# Turntable.net
KiCad netlist of a schematic drawn in EAGLE
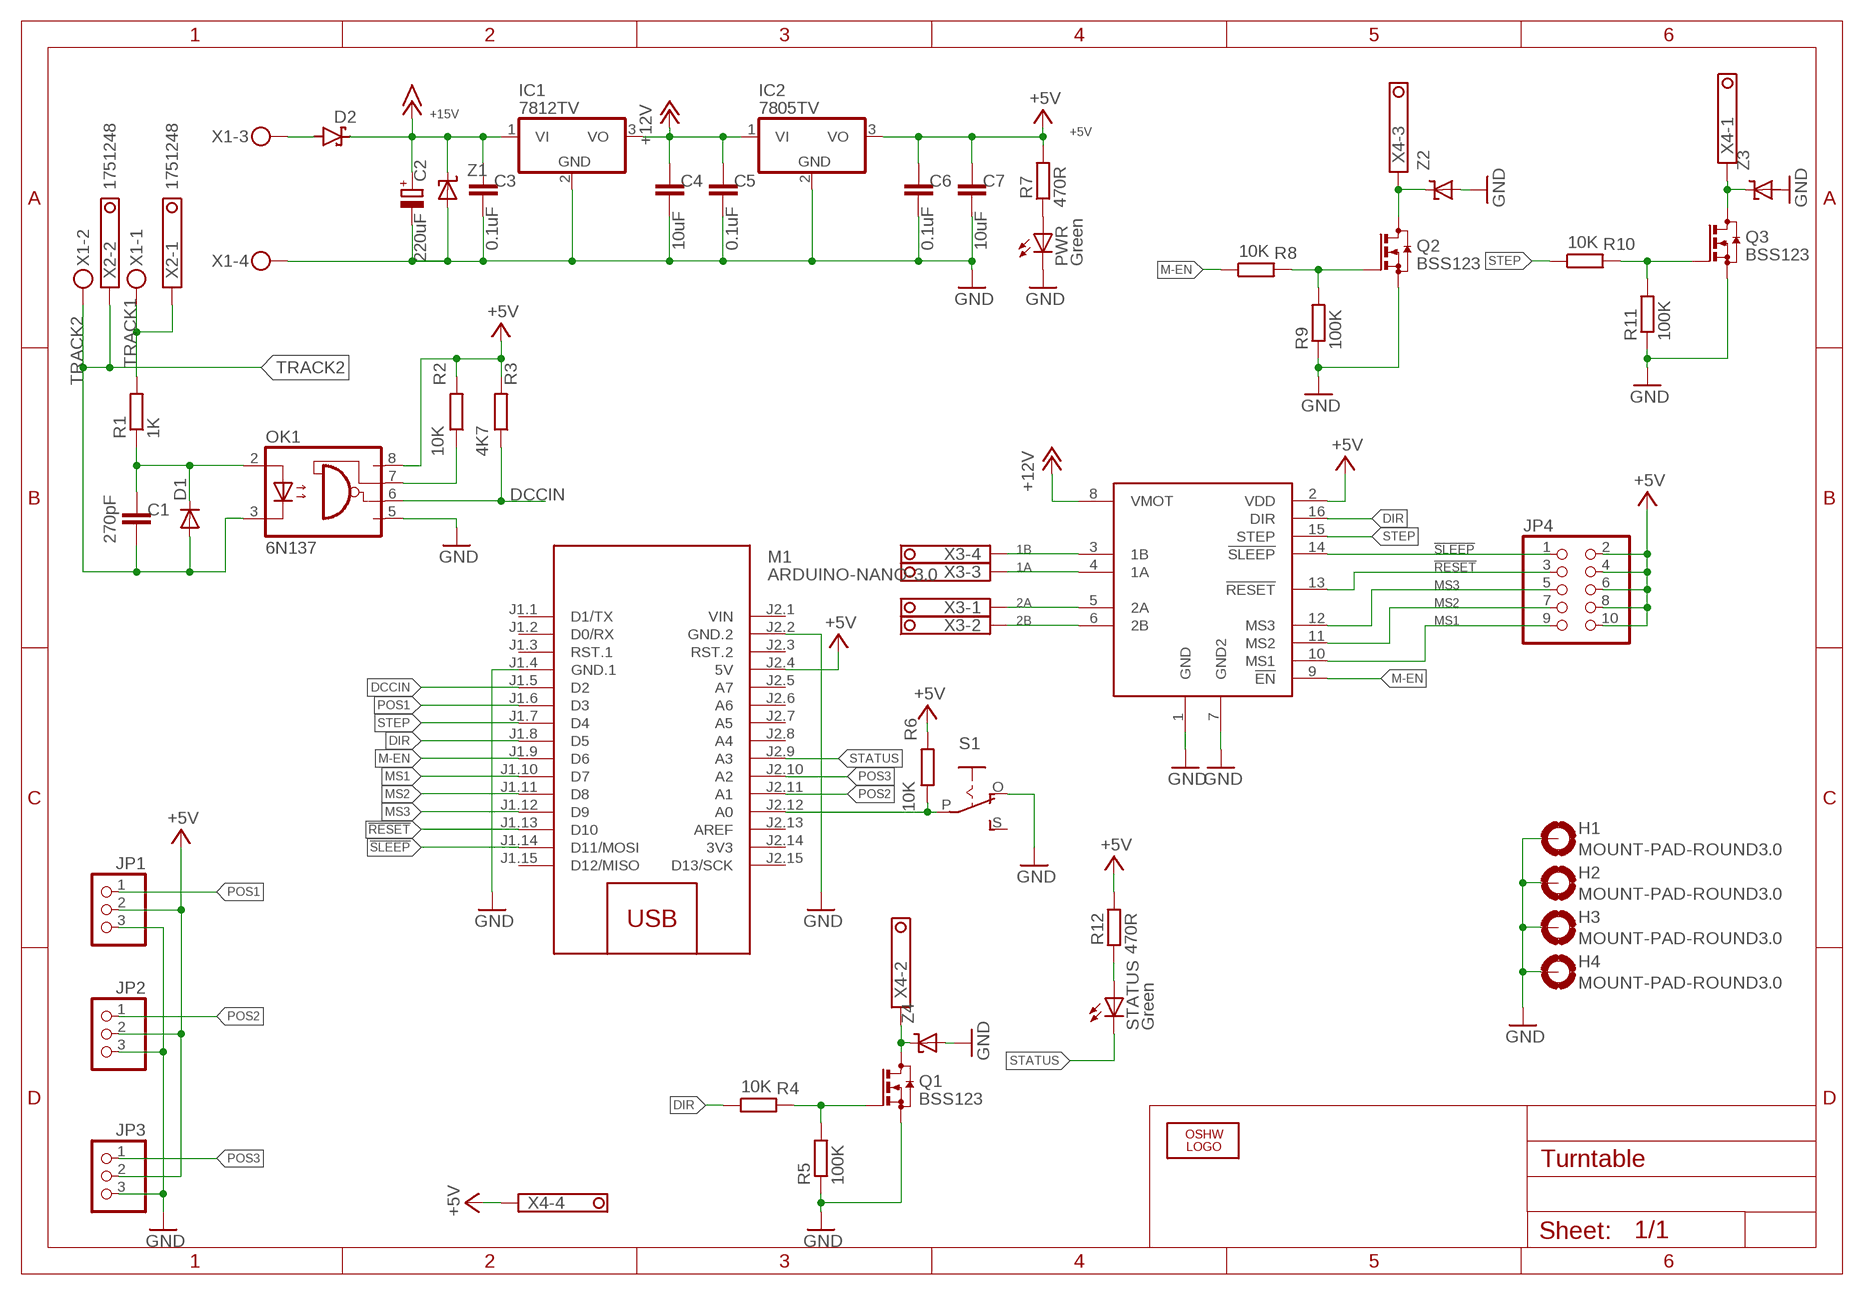
[diagram p0: schematic, sheet 1]

(export (version "E")
  (design (tool "Eeschema 10.0.6"))
  (components
    (comp (ref "C1")
      (value "270pF")
      (footprint "eagle-import:0805")
      (libsource (lib "eagle-import") (part "CAPACITOR-0805"))
    )
    (comp (ref "C2")
      (value "220uF")
      (footprint "eagle-import:E7,5-16")
      (libsource (lib "eagle-import") (part "CPOL-EUE7.5-16"))
    )
    (comp (ref "C3")
      (value "0.1uF")
      (footprint "eagle-import:0805")
      (libsource (lib "eagle-import") (part "CAPACITOR-0805"))
    )
    (comp (ref "C4")
      (value "10uF")
      (footprint "eagle-import:0805")
      (libsource (lib "eagle-import") (part "CAPACITOR-0805"))
    )
    (comp (ref "C5")
      (value "0.1uF")
      (footprint "eagle-import:0805")
      (libsource (lib "eagle-import") (part "CAPACITOR-0805"))
    )
    (comp (ref "C6")
      (value "0.1uF")
      (footprint "eagle-import:0805")
      (libsource (lib "eagle-import") (part "CAPACITOR-0805"))
    )
    (comp (ref "C7")
      (value "10uF")
      (footprint "eagle-import:0805")
      (libsource (lib "eagle-import") (part "CAPACITOR-0805"))
    )
    (comp (ref "D1")
      (value "CGRM4002-G")
      (footprint "eagle-import:SOD-123_MINI-SMA")
      (libsource (lib "eagle-import") (part "CGRM400-G2"))
    )
    (comp (ref "D2")
      (value "SCHOTTKY-DIODESMD")
      (footprint "eagle-import:SMB")
      (libsource (lib "eagle-import") (part "SCHOTTKY-DIODESMD"))
    )
    (comp (ref "H1")
      (value "MOUNT-PAD-ROUND3.0")
      (footprint "eagle-import:3,0-PAD")
      (libsource (lib "eagle-import") (part "MOUNT-PAD-ROUND3.0"))
    )
    (comp (ref "H2")
      (value "MOUNT-PAD-ROUND3.0")
      (footprint "eagle-import:3,0-PAD")
      (libsource (lib "eagle-import") (part "MOUNT-PAD-ROUND3.0"))
    )
    (comp (ref "H3")
      (value "MOUNT-PAD-ROUND3.0")
      (footprint "eagle-import:3,0-PAD")
      (libsource (lib "eagle-import") (part "MOUNT-PAD-ROUND3.0"))
    )
    (comp (ref "H4")
      (value "MOUNT-PAD-ROUND3.0")
      (footprint "eagle-import:3,0-PAD")
      (libsource (lib "eagle-import") (part "MOUNT-PAD-ROUND3.0"))
    )
    (comp (ref "IC1")
      (value "7812TV")
      (footprint "eagle-import:TO220V")
      (libsource (lib "eagle-import") (part "78TV12"))
    )
    (comp (ref "IC2")
      (value "7805TV")
      (footprint "eagle-import:TO220V")
      (libsource (lib "eagle-import") (part "78TV05"))
    )
    (comp (ref "JP1")
      (value "PINHD-1X3")
      (footprint "eagle-import:1X03")
      (libsource (lib "eagle-import") (part "PINHD-1X3"))
    )
    (comp (ref "JP2")
      (value "PINHD-1X3")
      (footprint "eagle-import:1X03")
      (libsource (lib "eagle-import") (part "PINHD-1X3"))
    )
    (comp (ref "JP3")
      (value "PINHD-1X3")
      (footprint "eagle-import:1X03")
      (libsource (lib "eagle-import") (part "PINHD-1X3"))
    )
    (comp (ref "JP4")
      (value "PINHD-2X5")
      (footprint "eagle-import:2X05")
      (libsource (lib "eagle-import") (part "PINHD-2X5"))
    )
    (comp (ref "LOGO1")
      (value "OSHW_LOGO_6MILX0200-NT")
      (footprint "eagle-import:OSHW_6X200_NOTEXT")
      (libsource (lib "eagle-import") (part "OSHW_LOGO_6MILX0200-NT"))
    )
    (comp (ref "M1")
      (value "ARDUINO-NANO-3.0")
      (footprint "eagle-import:ARDUINO-NANO-3.0")
      (libsource (lib "eagle-import") (part "ARDUINO-NANO-3.0"))
    )
    (comp (ref "OK1")
      (value "6N137")
      (footprint "eagle-import:DIL08")
      (libsource (lib "eagle-import") (part "6N137"))
    )
    (comp (ref "PWR")
      (value "Green")
      (footprint "eagle-import:LED3MM")
      (libsource (lib "eagle-import") (part "LED3MM"))
    )
    (comp (ref "Q1")
      (value "BSS123")
      (footprint "eagle-import:SOT23")
      (libsource (lib "eagle-import") (part "BSS123"))
    )
    (comp (ref "Q2")
      (value "BSS123")
      (footprint "eagle-import:SOT23")
      (libsource (lib "eagle-import") (part "BSS123"))
    )
    (comp (ref "Q3")
      (value "BSS123")
      (footprint "eagle-import:SOT23")
      (libsource (lib "eagle-import") (part "BSS123"))
    )
    (comp (ref "R1")
      (value "1K")
      (footprint "eagle-import:R0805")
      (libsource (lib "eagle-import") (part "RESISTORR0805-3D"))
    )
    (comp (ref "R2")
      (value "10K")
      (footprint "eagle-import:R0805")
      (libsource (lib "eagle-import") (part "RESISTORR0805-3D"))
    )
    (comp (ref "R3")
      (value "4K7")
      (footprint "eagle-import:R0805")
      (libsource (lib "eagle-import") (part "RESISTORR0805-3D"))
    )
    (comp (ref "R4")
      (value "10K")
      (footprint "eagle-import:R0805")
      (libsource (lib "eagle-import") (part "RESISTORR0805-3D"))
    )
    (comp (ref "R5")
      (value "100K")
      (footprint "eagle-import:R0805")
      (libsource (lib "eagle-import") (part "RESISTORR0805-3D"))
    )
    (comp (ref "R6")
      (value "10K")
      (footprint "eagle-import:R0805")
      (libsource (lib "eagle-import") (part "RESISTORR0805-3D"))
    )
    (comp (ref "R7")
      (value "470R")
      (footprint "eagle-import:R0805")
      (libsource (lib "eagle-import") (part "RESISTORR0805-3D"))
    )
    (comp (ref "R8")
      (value "10K")
      (footprint "eagle-import:R0805")
      (libsource (lib "eagle-import") (part "RESISTORR0805-3D"))
    )
    (comp (ref "R9")
      (value "100K")
      (footprint "eagle-import:R0805")
      (libsource (lib "eagle-import") (part "RESISTORR0805-3D"))
    )
    (comp (ref "R10")
      (value "10K")
      (footprint "eagle-import:R0805")
      (libsource (lib "eagle-import") (part "RESISTORR0805-3D"))
    )
    (comp (ref "R11")
      (value "100K")
      (footprint "eagle-import:R0805")
      (libsource (lib "eagle-import") (part "RESISTORR0805-3D"))
    )
    (comp (ref "R12")
      (value "470R")
      (footprint "eagle-import:R0805")
      (libsource (lib "eagle-import") (part "RESISTORR0805-3D"))
    )
    (comp (ref "S1")
      (value "EG1218S")
      (footprint "eagle-import:EG1218")
      (libsource (lib "eagle-import") (part "EG1218S"))
    )
    (comp (ref "STATUS")
      (value "Green")
      (footprint "eagle-import:LED3MM")
      (libsource (lib "eagle-import") (part "LED3MM"))
    )
    (comp (ref "U1")
      (value "A4988")
      (footprint "eagle-import:POLOLUA4988")
      (libsource (lib "eagle-import") (part "A4988"))
    )
    (comp (ref "X1")
      (value "MKDSN1,5/4-5,08")
      (footprint "eagle-import:MKDSN1,5_4-5,08")
      (fields (field (name "MPN") "SMKDSN1,5/4-5,08"))
      (libsource (lib "eagle-import") (part "MKDSN1,5/4-5,08"))
    )
    (comp (ref "X2")
      (value "1751248")
      (footprint "eagle-import:1751248")
      (libsource (lib "eagle-import") (part "1751248"))
    )
    (comp (ref "X3")
      (value "1751264")
      (footprint "eagle-import:1751264")
      (libsource (lib "eagle-import") (part "1751264"))
    )
    (comp (ref "X4")
      (value "1751264")
      (footprint "eagle-import:1751264")
      (libsource (lib "eagle-import") (part "1751264"))
    )
    (comp (ref "Z1")
      (value "MSMPX.X")
      (footprint "eagle-import:MICROSMP-T")
      (fields (field (name "MANUFACTURER") "VISHAY"))
      (libsource (lib "eagle-import") (part "MSMPX.X"))
    )
    (comp (ref "Z2")
      (value "MSMPX.X")
      (footprint "eagle-import:MICROSMP-T")
      (fields (field (name "MANUFACTURER") "VISHAY"))
      (libsource (lib "eagle-import") (part "MSMPX.X"))
    )
    (comp (ref "Z3")
      (value "MSMPX.X")
      (footprint "eagle-import:MICROSMP-T")
      (fields (field (name "MANUFACTURER") "VISHAY"))
      (libsource (lib "eagle-import") (part "MSMPX.X"))
    )
    (comp (ref "Z4")
      (value "MSMPX.X")
      (footprint "eagle-import:MICROSMP-T")
      (fields (field (name "MANUFACTURER") "VISHAY"))
      (libsource (lib "eagle-import") (part "MSMPX.X"))
    )
  )
  (nets
    (net (code "1") (name "+5V") (class "Default")
      (node (ref "C6") (pin "1") (pinfunction "1_1") (pintype "passive"))
      (node (ref "C7") (pin "1") (pinfunction "1_1") (pintype "passive"))
      (node (ref "IC2") (pin "3") (pinfunction "VO_3") (pintype "passive"))
      (node (ref "JP1") (pin "2") (pinfunction "2_2") (pintype "passive"))
      (node (ref "JP2") (pin "2") (pinfunction "2_2") (pintype "passive"))
      (node (ref "JP3") (pin "2") (pinfunction "2_2") (pintype "passive"))
      (node (ref "JP4") (pin "10") (pinfunction "10_10") (pintype "passive"))
      (node (ref "JP4") (pin "2") (pinfunction "2_2") (pintype "passive"))
      (node (ref "JP4") (pin "4") (pinfunction "4_4") (pintype "passive"))
      (node (ref "JP4") (pin "6") (pinfunction "6_6") (pintype "passive"))
      (node (ref "JP4") (pin "8") (pinfunction "8_8") (pintype "passive"))
      (node (ref "M1") (pin "J2.4") (pinfunction "5V_J2.4") (pintype "power_in"))
      (node (ref "OK1") (pin "8") (pinfunction "VCC_8") (pintype "passive"))
      (node (ref "R12") (pin "2") (pinfunction "2_2") (pintype "passive"))
      (node (ref "R2") (pin "2") (pinfunction "2_2") (pintype "passive"))
      (node (ref "R3") (pin "2") (pinfunction "2_2") (pintype "passive"))
      (node (ref "R6") (pin "2") (pinfunction "2_2") (pintype "passive"))
      (node (ref "R7") (pin "2") (pinfunction "2_2") (pintype "passive"))
      (node (ref "U1") (pin "2") (pinfunction "VDD_2") (pintype "power_in"))
      (node (ref "X4") (pin "4") (pinfunction "K_4") (pintype "passive"))
    )
    (net (code "2") (name "+12V") (class "Default")
      (node (ref "C4") (pin "1") (pinfunction "1_1") (pintype "passive"))
      (node (ref "C5") (pin "1") (pinfunction "1_1") (pintype "passive"))
      (node (ref "IC1") (pin "3") (pinfunction "VO_3") (pintype "passive"))
      (node (ref "IC2") (pin "1") (pinfunction "VI_1") (pintype "input"))
      (node (ref "U1") (pin "8") (pinfunction "VMOT_8") (pintype "bidirectional"))
    )
    (net (code "3") (name "+15V") (class "Default")
      (node (ref "C2") (pin "+") (pinfunction "+_+") (pintype "passive"))
      (node (ref "C3") (pin "1") (pinfunction "1_1") (pintype "passive"))
      (node (ref "D2") (pin "C") (pinfunction "C_C") (pintype "passive"))
      (node (ref "IC1") (pin "1") (pinfunction "VI_1") (pintype "input"))
      (node (ref "Z1") (pin "C") (pinfunction "C_C") (pintype "passive"))
    )
    (net (code "4") (name "/1A") (class "Default")
      (node (ref "U1") (pin "4") (pinfunction "1A_4") (pintype "open_collector"))
      (node (ref "X3") (pin "3") (pinfunction "K_3") (pintype "passive"))
    )
    (net (code "5") (name "/1B") (class "Default")
      (node (ref "U1") (pin "3") (pinfunction "1B_3") (pintype "open_collector"))
      (node (ref "X3") (pin "4") (pinfunction "K_4") (pintype "passive"))
    )
    (net (code "6") (name "/2A") (class "Default")
      (node (ref "U1") (pin "5") (pinfunction "2A_5") (pintype "open_collector"))
      (node (ref "X3") (pin "1") (pinfunction "K_1") (pintype "passive"))
    )
    (net (code "7") (name "/2B") (class "Default")
      (node (ref "U1") (pin "6") (pinfunction "2B_6") (pintype "open_collector"))
      (node (ref "X3") (pin "2") (pinfunction "K_2") (pintype "passive"))
    )
    (net (code "8") (name "/3V3") (class "Default")
      (node (ref "M1") (pin "J2.14") (pinfunction "3V3_J2.14") (pintype "power_in"))
    )
    (net (code "9") (name "/TRACK1") (class "Default")
      (node (ref "R1") (pin "2") (pinfunction "2_2") (pintype "passive"))
      (node (ref "X1") (pin "1") (pinfunction "KL_1") (pintype "passive"))
      (node (ref "X2") (pin "1") (pinfunction "K_1") (pintype "passive"))
    )
    (net (code "10") (name "/VIN") (class "Default")
      (node (ref "M1") (pin "J2.1") (pinfunction "VIN_J2.1") (pintype "power_in"))
    )
    (net (code "11") (name "/~{RESET}") (class "Default")
      (node (ref "JP4") (pin "3") (pinfunction "3_3") (pintype "passive"))
      (node (ref "M1") (pin "J1.13") (pinfunction "D10_J1.13") (pintype "bidirectional"))
      (node (ref "U1") (pin "13") (pinfunction "~{RESET}_13") (pintype "input"))
    )
    (net (code "12") (name "/~{SLEEP}") (class "Default")
      (node (ref "JP4") (pin "1") (pinfunction "1_1") (pintype "passive"))
      (node (ref "M1") (pin "J1.14") (pinfunction "D11/MOSI_J1.14") (pintype "bidirectional"))
      (node (ref "U1") (pin "14") (pinfunction "~{SLEEP}_14") (pintype "input"))
    )
    (net (code "13") (name "DCCIN") (class "Default")
      (node (ref "M1") (pin "J1.5") (pinfunction "D2_J1.5") (pintype "bidirectional"))
      (node (ref "OK1") (pin "6") (pinfunction "VO_6") (pintype "passive"))
      (node (ref "R3") (pin "1") (pinfunction "1_1") (pintype "passive"))
    )
    (net (code "14") (name "DIR") (class "Default")
      (node (ref "M1") (pin "J1.8") (pinfunction "D5_J1.8") (pintype "bidirectional"))
      (node (ref "R4") (pin "1") (pinfunction "1_1") (pintype "passive"))
      (node (ref "U1") (pin "16") (pinfunction "DIR_16") (pintype "input"))
    )
    (net (code "15") (name "GND") (class "Default")
      (node (ref "C2") (pin "-") (pinfunction "-_-") (pintype "passive"))
      (node (ref "C3") (pin "2") (pinfunction "2_2") (pintype "passive"))
      (node (ref "C4") (pin "2") (pinfunction "2_2") (pintype "passive"))
      (node (ref "C5") (pin "2") (pinfunction "2_2") (pintype "passive"))
      (node (ref "C6") (pin "2") (pinfunction "2_2") (pintype "passive"))
      (node (ref "C7") (pin "2") (pinfunction "2_2") (pintype "passive"))
      (node (ref "H1") (pin "B3,0") (pinfunction "MOUNT_B3,0") (pintype "passive"))
      (node (ref "H2") (pin "B3,0") (pinfunction "MOUNT_B3,0") (pintype "passive"))
      (node (ref "H3") (pin "B3,0") (pinfunction "MOUNT_B3,0") (pintype "passive"))
      (node (ref "H4") (pin "B3,0") (pinfunction "MOUNT_B3,0") (pintype "passive"))
      (node (ref "IC1") (pin "2") (pinfunction "GND_2") (pintype "passive"))
      (node (ref "IC2") (pin "2") (pinfunction "GND_2") (pintype "passive"))
      (node (ref "JP1") (pin "3") (pinfunction "3_3") (pintype "passive"))
      (node (ref "JP2") (pin "3") (pinfunction "3_3") (pintype "passive"))
      (node (ref "JP3") (pin "3") (pinfunction "3_3") (pintype "passive"))
      (node (ref "M1") (pin "J1.4") (pinfunction "GND.1_J1.4") (pintype "power_in"))
      (node (ref "M1") (pin "J2.2") (pinfunction "GND.2_J2.2") (pintype "power_in"))
      (node (ref "OK1") (pin "5") (pinfunction "GND_5") (pintype "passive"))
      (node (ref "PWR") (pin "K") (pinfunction "C_K") (pintype "passive"))
      (node (ref "Q1") (pin "2") (pinfunction "S_2") (pintype "passive"))
      (node (ref "Q2") (pin "2") (pinfunction "S_2") (pintype "passive"))
      (node (ref "Q3") (pin "2") (pinfunction "S_2") (pintype "passive"))
      (node (ref "R11") (pin "1") (pinfunction "1_1") (pintype "passive"))
      (node (ref "R5") (pin "1") (pinfunction "1_1") (pintype "passive"))
      (node (ref "R9") (pin "1") (pinfunction "1_1") (pintype "passive"))
      (node (ref "S1") (pin "O") (pinfunction "O_O") (pintype "passive"))
      (node (ref "U1") (pin "1") (pinfunction "GND_1") (pintype "passive"))
      (node (ref "U1") (pin "7") (pinfunction "GND2_7") (pintype "bidirectional"))
      (node (ref "X1") (pin "4") (pinfunction "KL_4") (pintype "passive"))
      (node (ref "Z1") (pin "A") (pinfunction "A_A") (pintype "passive"))
      (node (ref "Z2") (pin "A") (pinfunction "A_A") (pintype "passive"))
      (node (ref "Z4") (pin "A") (pinfunction "A_A") (pintype "passive"))
    )
    (net (code "16") (name "M-EN") (class "Default")
      (node (ref "M1") (pin "J1.9") (pinfunction "D6_J1.9") (pintype "bidirectional"))
      (node (ref "R8") (pin "1") (pinfunction "1_1") (pintype "passive"))
      (node (ref "U1") (pin "9") (pinfunction "~{EN}_9") (pintype "input"))
    )
    (net (code "17") (name "MS1") (class "Default")
      (node (ref "JP4") (pin "9") (pinfunction "9_9") (pintype "passive"))
      (node (ref "M1") (pin "J1.10") (pinfunction "D7_J1.10") (pintype "bidirectional"))
      (node (ref "U1") (pin "10") (pinfunction "MS1_10") (pintype "input"))
    )
    (net (code "18") (name "MS2") (class "Default")
      (node (ref "JP4") (pin "7") (pinfunction "7_7") (pintype "passive"))
      (node (ref "M1") (pin "J1.11") (pinfunction "D8_J1.11") (pintype "bidirectional"))
      (node (ref "U1") (pin "11") (pinfunction "MS2_11") (pintype "input"))
    )
    (net (code "19") (name "MS3") (class "Default")
      (node (ref "JP4") (pin "5") (pinfunction "5_5") (pintype "passive"))
      (node (ref "M1") (pin "J1.12") (pinfunction "D9_J1.12") (pintype "bidirectional"))
      (node (ref "U1") (pin "12") (pinfunction "MS3_12") (pintype "input"))
    )
    (net (code "20") (name "Net-(M1-A0)") (class "Default")
      (node (ref "M1") (pin "J2.12") (pinfunction "A0_J2.12") (pintype "bidirectional"))
      (node (ref "R6") (pin "1") (pinfunction "1_1") (pintype "passive"))
      (node (ref "S1") (pin "P") (pinfunction "P_P") (pintype "passive"))
    )
    (net (code "21") (name "Net-(OK1-A)") (class "Default")
      (node (ref "C1") (pin "1") (pinfunction "1_1") (pintype "passive"))
      (node (ref "D1") (pin "C") (pinfunction "C_C") (pintype "passive"))
      (node (ref "OK1") (pin "2") (pinfunction "A_2") (pintype "passive"))
      (node (ref "R1") (pin "1") (pinfunction "1_1") (pintype "passive"))
    )
    (net (code "22") (name "Net-(OK1-VE)") (class "Default")
      (node (ref "OK1") (pin "7") (pinfunction "VE_7") (pintype "passive"))
      (node (ref "R2") (pin "1") (pinfunction "1_1") (pintype "passive"))
    )
    (net (code "23") (name "Net-(PWR-PadA)") (class "Default")
      (node (ref "PWR") (pin "A") (pinfunction "A_A") (pintype "passive"))
      (node (ref "R7") (pin "1") (pinfunction "1_1") (pintype "passive"))
    )
    (net (code "24") (name "Net-(Q1-D)") (class "Default")
      (node (ref "Q1") (pin "3") (pinfunction "D_3") (pintype "passive"))
      (node (ref "X4") (pin "2") (pinfunction "K_2") (pintype "passive"))
      (node (ref "Z4") (pin "C") (pinfunction "C_C") (pintype "passive"))
    )
    (net (code "25") (name "Net-(Q1-G)") (class "Default")
      (node (ref "Q1") (pin "1") (pinfunction "G_1") (pintype "passive"))
      (node (ref "R4") (pin "2") (pinfunction "2_2") (pintype "passive"))
      (node (ref "R5") (pin "2") (pinfunction "2_2") (pintype "passive"))
    )
    (net (code "26") (name "Net-(Q2-D)") (class "Default")
      (node (ref "Q2") (pin "3") (pinfunction "D_3") (pintype "passive"))
      (node (ref "X4") (pin "3") (pinfunction "K_3") (pintype "passive"))
      (node (ref "Z2") (pin "C") (pinfunction "C_C") (pintype "passive"))
    )
    (net (code "27") (name "Net-(Q2-G)") (class "Default")
      (node (ref "Q2") (pin "1") (pinfunction "G_1") (pintype "passive"))
      (node (ref "R8") (pin "2") (pinfunction "2_2") (pintype "passive"))
      (node (ref "R9") (pin "2") (pinfunction "2_2") (pintype "passive"))
    )
    (net (code "28") (name "Net-(Q3-D)") (class "Default")
      (node (ref "Q3") (pin "3") (pinfunction "D_3") (pintype "passive"))
      (node (ref "X4") (pin "1") (pinfunction "K_1") (pintype "passive"))
      (node (ref "Z3") (pin "C") (pinfunction "C_C") (pintype "passive"))
    )
    (net (code "29") (name "Net-(Q3-G)") (class "Default")
      (node (ref "Q3") (pin "1") (pinfunction "G_1") (pintype "passive"))
      (node (ref "R10") (pin "2") (pinfunction "2_2") (pintype "passive"))
      (node (ref "R11") (pin "2") (pinfunction "2_2") (pintype "passive"))
    )
    (net (code "30") (name "Net-(R12-Pad1)") (class "Default")
      (node (ref "R12") (pin "1") (pinfunction "1_1") (pintype "passive"))
      (node (ref "STATUS") (pin "A") (pinfunction "A_A") (pintype "passive"))
    )
    (net (code "31") (name "Net-(X1C-KL)") (class "Default")
      (node (ref "D2") (pin "A") (pinfunction "A_A") (pintype "passive"))
      (node (ref "X1") (pin "3") (pinfunction "KL_3") (pintype "passive"))
    )
    (net (code "32") (name "POS1") (class "Default")
      (node (ref "JP1") (pin "1") (pinfunction "1_1") (pintype "passive"))
      (node (ref "M1") (pin "J1.6") (pinfunction "D3_J1.6") (pintype "bidirectional"))
    )
    (net (code "33") (name "POS2") (class "Default")
      (node (ref "JP2") (pin "1") (pinfunction "1_1") (pintype "passive"))
      (node (ref "M1") (pin "J2.11") (pinfunction "A1_J2.11") (pintype "bidirectional"))
    )
    (net (code "34") (name "POS3") (class "Default")
      (node (ref "JP3") (pin "1") (pinfunction "1_1") (pintype "passive"))
      (node (ref "M1") (pin "J2.10") (pinfunction "A2_J2.10") (pintype "bidirectional"))
    )
    (net (code "35") (name "STATUS") (class "Default")
      (node (ref "M1") (pin "J2.9") (pinfunction "A3_J2.9") (pintype "bidirectional"))
      (node (ref "STATUS") (pin "K") (pinfunction "C_K") (pintype "passive"))
    )
    (net (code "36") (name "STEP") (class "Default")
      (node (ref "M1") (pin "J1.7") (pinfunction "D4_J1.7") (pintype "bidirectional"))
      (node (ref "R10") (pin "1") (pinfunction "1_1") (pintype "passive"))
      (node (ref "U1") (pin "15") (pinfunction "STEP_15") (pintype "input"))
    )
    (net (code "37") (name "TRACK2") (class "Default")
      (node (ref "C1") (pin "2") (pinfunction "2_2") (pintype "passive"))
      (node (ref "D1") (pin "A") (pinfunction "A_A") (pintype "passive"))
      (node (ref "OK1") (pin "3") (pinfunction "C_3") (pintype "passive"))
      (node (ref "X1") (pin "2") (pinfunction "KL_2") (pintype "passive"))
      (node (ref "X2") (pin "2") (pinfunction "K_2") (pintype "passive"))
    )
    (net (code "38") (name "unconnected-(M1-A4-PadJ2.8)") (class "Default")
      (node (ref "M1") (pin "J2.8") (pinfunction "A4_J2.8") (pintype "bidirectional"))
    )
    (net (code "39") (name "unconnected-(M1-A5-PadJ2.7)") (class "Default")
      (node (ref "M1") (pin "J2.7") (pinfunction "A5_J2.7") (pintype "bidirectional"))
    )
    (net (code "40") (name "unconnected-(M1-A6-PadJ2.6)") (class "Default")
      (node (ref "M1") (pin "J2.6") (pinfunction "A6_J2.6") (pintype "bidirectional"))
    )
    (net (code "41") (name "unconnected-(M1-A7-PadJ2.5)") (class "Default")
      (node (ref "M1") (pin "J2.5") (pinfunction "A7_J2.5") (pintype "bidirectional"))
    )
    (net (code "42") (name "unconnected-(M1-AREF-PadJ2.13)") (class "Default")
      (node (ref "M1") (pin "J2.13") (pinfunction "AREF_J2.13") (pintype "bidirectional"))
    )
    (net (code "43") (name "unconnected-(M1-D0{slash}RX-PadJ1.2)") (class "Default")
      (node (ref "M1") (pin "J1.2") (pinfunction "D0/RX_J1.2") (pintype "bidirectional"))
    )
    (net (code "44") (name "unconnected-(M1-D1{slash}TX-PadJ1.1)") (class "Default")
      (node (ref "M1") (pin "J1.1") (pinfunction "D1/TX_J1.1") (pintype "bidirectional"))
    )
    (net (code "45") (name "unconnected-(M1-D12{slash}MISO-PadJ1.15)") (class "Default")
      (node (ref "M1") (pin "J1.15") (pinfunction "D12/MISO_J1.15") (pintype "bidirectional"))
    )
    (net (code "46") (name "unconnected-(M1-D13{slash}SCK-PadJ2.15)") (class "Default")
      (node (ref "M1") (pin "J2.15") (pinfunction "D13/SCK_J2.15") (pintype "bidirectional"))
    )
    (net (code "47") (name "unconnected-(M1-RST.1-PadJ1.3)") (class "Default")
      (node (ref "M1") (pin "J1.3") (pinfunction "RST.1_J1.3") (pintype "bidirectional"))
    )
    (net (code "48") (name "unconnected-(M1-RST.2-PadJ2.3)") (class "Default")
      (node (ref "M1") (pin "J2.3") (pinfunction "RST.2_J2.3") (pintype "bidirectional"))
    )
    (net (code "49") (name "unconnected-(S1-PadS)") (class "Default")
      (node (ref "S1") (pin "S") (pinfunction "S_S") (pintype "passive"))
    )
    (net (code "50") (name "unconnected-(Z3-PadA)") (class "Default")
      (node (ref "Z3") (pin "A") (pinfunction "A_A") (pintype "passive"))
    )
  )
)
